# Z05_C8V_A_01.net
KiCad netlist of a schematic drawn in EAGLE
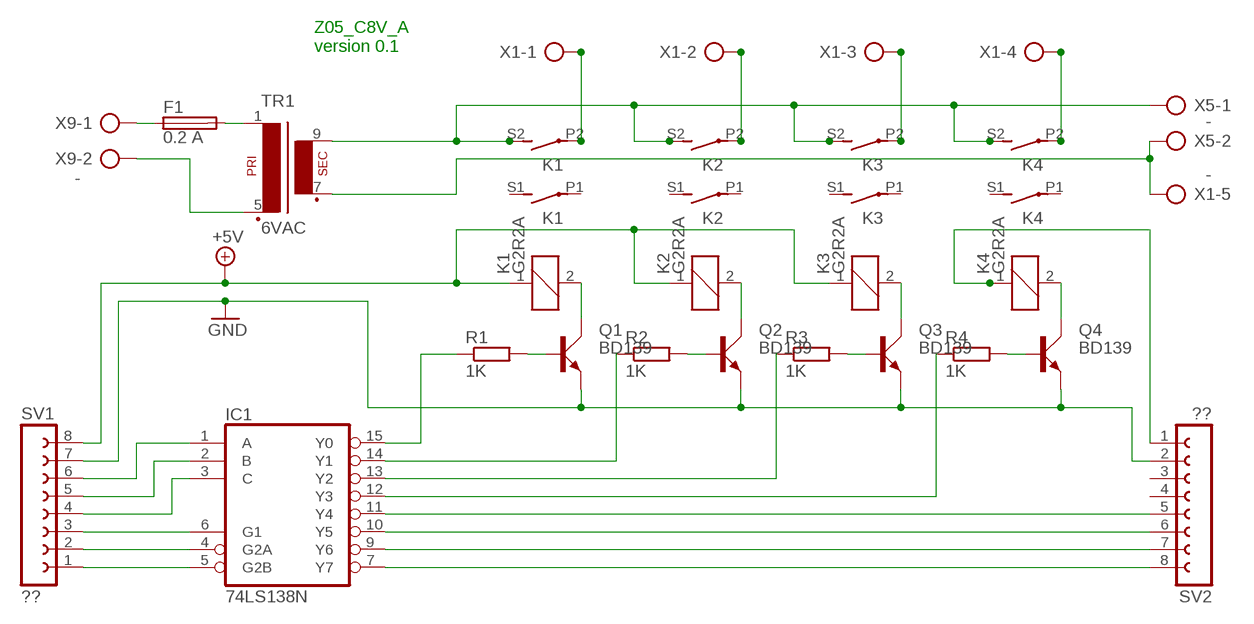
[diagram p0: schematic, sheet 1]

(export (version "E")
  (design (tool "Eeschema 10.0.6"))
  (components
    (comp (ref "F1")
      (value "0.2 A")
      (footprint "eagle-import:GSH15")
      (fields (field (name "MPN") "64900001039"))
      (libsource (lib "eagle-import") (part "GSH15"))
    )
    (comp (ref "IC1")
      (value "74LS138N")
      (footprint "eagle-import:DIL16")
      (libsource (lib "eagle-import") (part "74138NLS"))
    )
    (comp (ref "K1")
      (value "G2R2A")
      (footprint "eagle-import:G2R2A")
      (fields (field (name "MPN") "G2R-2A-DC24"))
      (libsource (lib "eagle-import") (part "G2R2A"))
    )
    (comp (ref "K2")
      (value "G2R2A")
      (footprint "eagle-import:G2R2A")
      (fields (field (name "MPN") "G2R-2A-DC24"))
      (libsource (lib "eagle-import") (part "G2R2A"))
    )
    (comp (ref "K3")
      (value "G2R2A")
      (footprint "eagle-import:G2R2A")
      (fields (field (name "MPN") "G2R-2A-DC24"))
      (libsource (lib "eagle-import") (part "G2R2A"))
    )
    (comp (ref "K4")
      (value "G2R2A")
      (footprint "eagle-import:G2R2A")
      (fields (field (name "MPN") "G2R-2A-DC24"))
      (libsource (lib "eagle-import") (part "G2R2A"))
    )
    (comp (ref "Q1")
      (value "BD139")
      (footprint "eagle-import:TO126AV")
      (libsource (lib "eagle-import") (part "BD139"))
    )
    (comp (ref "Q2")
      (value "BD139")
      (footprint "eagle-import:TO126AV")
      (libsource (lib "eagle-import") (part "BD139"))
    )
    (comp (ref "Q3")
      (value "BD139")
      (footprint "eagle-import:TO126AV")
      (libsource (lib "eagle-import") (part "BD139"))
    )
    (comp (ref "Q4")
      (value "BD139")
      (footprint "eagle-import:TO126AV")
      (libsource (lib "eagle-import") (part "BD139"))
    )
    (comp (ref "R1")
      (value "1K")
      (footprint "eagle-import:0204_7")
      (libsource (lib "eagle-import") (part "R-EU_0204/7"))
    )
    (comp (ref "R2")
      (value "1K")
      (footprint "eagle-import:0204_7")
      (libsource (lib "eagle-import") (part "R-EU_0204/7"))
    )
    (comp (ref "R3")
      (value "1K")
      (footprint "eagle-import:0204_7")
      (libsource (lib "eagle-import") (part "R-EU_0204/7"))
    )
    (comp (ref "R4")
      (value "1K")
      (footprint "eagle-import:0204_7")
      (libsource (lib "eagle-import") (part "R-EU_0204/7"))
    )
    (comp (ref "SV1")
      (value "??")
      (footprint "eagle-import:FE08W")
      (libsource (lib "eagle-import") (part "FE08W"))
    )
    (comp (ref "SV2")
      (value "??")
      (footprint "eagle-import:FE08W")
      (fields (field (name "OC_FARNELL") "unknown") (field (name "OC_NEWARK") "unknown"))
      (libsource (lib "eagle-import") (part "FE08W"))
    )
    (comp (ref "TR1")
      (value "6VAC")
      (footprint "eagle-import:EI42-1")
      (libsource (lib "eagle-import") (part "EI42-1"))
    )
    (comp (ref "X1")
      (value "-")
      (footprint "eagle-import:AK300_5")
      (libsource (lib "eagle-import") (part "AK300/5"))
    )
    (comp (ref "X5")
      (value "-")
      (footprint "eagle-import:AK300_2")
      (libsource (lib "eagle-import") (part "AK300/2"))
    )
    (comp (ref "X9")
      (value "-")
      (footprint "eagle-import:AK300_2")
      (libsource (lib "eagle-import") (part "AK300/2"))
    )
  )
  (nets
    (net (code "1") (name "+5V") (class "Default")
      (node (ref "K1") (pin "1") (pinfunction "1_1") (pintype "passive"))
      (node (ref "K2") (pin "1") (pinfunction "1_1") (pintype "passive"))
      (node (ref "K3") (pin "1") (pinfunction "1_1") (pintype "passive"))
      (node (ref "SV1") (pin "8") (pinfunction "8_8") (pintype "passive"))
    )
    (net (code "2") (name "/N$38") (class "Default")
      (node (ref "K1") (pin "P2") (pinfunction "P_P2") (pintype "passive"))
      (node (ref "K2") (pin "P2") (pinfunction "P_P2") (pintype "passive"))
      (node (ref "K3") (pin "P2") (pinfunction "P_P2") (pintype "passive"))
      (node (ref "K4") (pin "P2") (pinfunction "P_P2") (pintype "passive"))
      (node (ref "X1") (pin "1") (pinfunction "KL_1") (pintype "passive"))
      (node (ref "X1") (pin "2") (pinfunction "KL_2") (pintype "passive"))
      (node (ref "X1") (pin "3") (pinfunction "KL_3") (pintype "passive"))
      (node (ref "X1") (pin "4") (pinfunction "KL_4") (pintype "passive"))
    )
    (net (code "3") (name "GND") (class "Default")
      (node (ref "Q1") (pin "E") (pinfunction "E_E") (pintype "passive"))
      (node (ref "Q2") (pin "E") (pinfunction "E_E") (pintype "passive"))
      (node (ref "Q3") (pin "E") (pinfunction "E_E") (pintype "passive"))
      (node (ref "Q4") (pin "E") (pinfunction "E_E") (pintype "passive"))
      (node (ref "SV1") (pin "7") (pinfunction "7_7") (pintype "passive"))
      (node (ref "SV2") (pin "2") (pinfunction "2_2") (pintype "passive"))
    )
    (net (code "4") (name "Net-(IC1A-A)") (class "Default")
      (node (ref "IC1") (pin "1") (pinfunction "A_1") (pintype "input"))
      (node (ref "SV1") (pin "6") (pinfunction "6_6") (pintype "passive"))
    )
    (net (code "5") (name "Net-(IC1A-B)") (class "Default")
      (node (ref "IC1") (pin "2") (pinfunction "B_2") (pintype "input"))
      (node (ref "SV1") (pin "5") (pinfunction "5_5") (pintype "passive"))
    )
    (net (code "6") (name "Net-(IC1A-C)") (class "Default")
      (node (ref "IC1") (pin "3") (pinfunction "C_3") (pintype "input"))
      (node (ref "SV1") (pin "4") (pinfunction "4_4") (pintype "passive"))
    )
    (net (code "7") (name "Net-(IC1A-G1)") (class "Default")
      (node (ref "IC1") (pin "6") (pinfunction "G1_6") (pintype "input"))
      (node (ref "SV1") (pin "3") (pinfunction "3_3") (pintype "passive"))
    )
    (net (code "8") (name "Net-(IC1A-G2A)") (class "Default")
      (node (ref "IC1") (pin "4") (pinfunction "G2A_4") (pintype "input"))
      (node (ref "SV1") (pin "2") (pinfunction "2_2") (pintype "passive"))
    )
    (net (code "9") (name "Net-(IC1A-G2B)") (class "Default")
      (node (ref "IC1") (pin "5") (pinfunction "G2B_5") (pintype "input"))
      (node (ref "SV1") (pin "1") (pinfunction "1_1") (pintype "passive"))
    )
    (net (code "10") (name "Net-(IC1A-Y0)") (class "Default")
      (node (ref "IC1") (pin "15") (pinfunction "Y0_15") (pintype "output"))
      (node (ref "R1") (pin "1") (pinfunction "1_1") (pintype "passive"))
    )
    (net (code "11") (name "Net-(IC1A-Y1)") (class "Default")
      (node (ref "IC1") (pin "14") (pinfunction "Y1_14") (pintype "output"))
      (node (ref "R2") (pin "1") (pinfunction "1_1") (pintype "passive"))
    )
    (net (code "12") (name "Net-(IC1A-Y2)") (class "Default")
      (node (ref "IC1") (pin "13") (pinfunction "Y2_13") (pintype "output"))
      (node (ref "R3") (pin "1") (pinfunction "1_1") (pintype "passive"))
    )
    (net (code "13") (name "Net-(IC1A-Y3)") (class "Default")
      (node (ref "IC1") (pin "12") (pinfunction "Y3_12") (pintype "output"))
      (node (ref "R4") (pin "1") (pinfunction "1_1") (pintype "passive"))
    )
    (net (code "14") (name "Net-(IC1A-Y4)") (class "Default")
      (node (ref "IC1") (pin "11") (pinfunction "Y4_11") (pintype "output"))
      (node (ref "SV2") (pin "5") (pinfunction "5_5") (pintype "passive"))
    )
    (net (code "15") (name "Net-(IC1A-Y5)") (class "Default")
      (node (ref "IC1") (pin "10") (pinfunction "Y5_10") (pintype "output"))
      (node (ref "SV2") (pin "6") (pinfunction "6_6") (pintype "passive"))
    )
    (net (code "16") (name "Net-(IC1A-Y6)") (class "Default")
      (node (ref "IC1") (pin "9") (pinfunction "Y6_9") (pintype "output"))
      (node (ref "SV2") (pin "7") (pinfunction "7_7") (pintype "passive"))
    )
    (net (code "17") (name "Net-(IC1A-Y7)") (class "Default")
      (node (ref "IC1") (pin "7") (pinfunction "Y7_7") (pintype "output"))
      (node (ref "SV2") (pin "8") (pinfunction "8_8") (pintype "passive"))
    )
    (net (code "18") (name "Net-(K1-Pad2)") (class "Default")
      (node (ref "K1") (pin "2") (pinfunction "2_2") (pintype "passive"))
      (node (ref "Q1") (pin "C") (pinfunction "C_C") (pintype "passive"))
    )
    (net (code "19") (name "Net-(K1C-S)") (class "Default")
      (node (ref "K1") (pin "S2") (pinfunction "S_S2") (pintype "passive"))
      (node (ref "K2") (pin "S2") (pinfunction "S_S2") (pintype "passive"))
      (node (ref "K3") (pin "S2") (pinfunction "S_S2") (pintype "passive"))
      (node (ref "K4") (pin "S2") (pinfunction "S_S2") (pintype "passive"))
      (node (ref "TR1") (pin "9") (pinfunction "S4_9") (pintype "passive"))
      (node (ref "X5") (pin "1") (pinfunction "KL_1") (pintype "passive"))
    )
    (net (code "20") (name "Net-(K2-Pad2)") (class "Default")
      (node (ref "K2") (pin "2") (pinfunction "2_2") (pintype "passive"))
      (node (ref "Q2") (pin "C") (pinfunction "C_C") (pintype "passive"))
    )
    (net (code "21") (name "Net-(K3-Pad2)") (class "Default")
      (node (ref "K3") (pin "2") (pinfunction "2_2") (pintype "passive"))
      (node (ref "Q3") (pin "C") (pinfunction "C_C") (pintype "passive"))
    )
    (net (code "22") (name "Net-(K4-Pad1)") (class "Default")
      (node (ref "K4") (pin "1") (pinfunction "1_1") (pintype "passive"))
      (node (ref "SV2") (pin "1") (pinfunction "1_1") (pintype "passive"))
    )
    (net (code "23") (name "Net-(K4-Pad2)") (class "Default")
      (node (ref "K4") (pin "2") (pinfunction "2_2") (pintype "passive"))
      (node (ref "Q4") (pin "C") (pinfunction "C_C") (pintype "passive"))
    )
    (net (code "24") (name "Net-(Q1-PadB)") (class "Default")
      (node (ref "Q1") (pin "B") (pinfunction "B_B") (pintype "passive"))
      (node (ref "R1") (pin "2") (pinfunction "2_2") (pintype "passive"))
    )
    (net (code "25") (name "Net-(Q2-PadB)") (class "Default")
      (node (ref "Q2") (pin "B") (pinfunction "B_B") (pintype "passive"))
      (node (ref "R2") (pin "2") (pinfunction "2_2") (pintype "passive"))
    )
    (net (code "26") (name "Net-(Q3-PadB)") (class "Default")
      (node (ref "Q3") (pin "B") (pinfunction "B_B") (pintype "passive"))
      (node (ref "R3") (pin "2") (pinfunction "2_2") (pintype "passive"))
    )
    (net (code "27") (name "Net-(Q4-PadB)") (class "Default")
      (node (ref "Q4") (pin "B") (pinfunction "B_B") (pintype "passive"))
      (node (ref "R4") (pin "2") (pinfunction "2_2") (pintype "passive"))
    )
    (net (code "28") (name "Net-(TR1-P1)") (class "Default")
      (node (ref "F1") (pin "2") (pinfunction "2_2") (pintype "passive"))
      (node (ref "TR1") (pin "1") (pinfunction "P1_1") (pintype "passive"))
    )
    (net (code "29") (name "Net-(TR1-P2)") (class "Default")
      (node (ref "TR1") (pin "5") (pinfunction "P2_5") (pintype "passive"))
      (node (ref "X9") (pin "2") (pinfunction "KL_2") (pintype "passive"))
    )
    (net (code "30") (name "Net-(TR1-S3)") (class "Default")
      (node (ref "TR1") (pin "7") (pinfunction "S3_7") (pintype "passive"))
      (node (ref "X1") (pin "5") (pinfunction "KL_5") (pintype "passive"))
      (node (ref "X5") (pin "2") (pinfunction "KL_2") (pintype "passive"))
    )
    (net (code "31") (name "Net-(X9A-KL)") (class "Default")
      (node (ref "F1") (pin "1") (pinfunction "1_1") (pintype "passive"))
      (node (ref "X9") (pin "1") (pinfunction "KL_1") (pintype "passive"))
    )
    (net (code "32") (name "unconnected-(K1B-P-PadP1)") (class "Default")
      (node (ref "K1") (pin "P1") (pinfunction "P_P1") (pintype "passive"))
    )
    (net (code "33") (name "unconnected-(K1B-S-PadS1)") (class "Default")
      (node (ref "K1") (pin "S1") (pinfunction "S_S1") (pintype "passive"))
    )
    (net (code "34") (name "unconnected-(K2B-P-PadP1)") (class "Default")
      (node (ref "K2") (pin "P1") (pinfunction "P_P1") (pintype "passive"))
    )
    (net (code "35") (name "unconnected-(K2B-S-PadS1)") (class "Default")
      (node (ref "K2") (pin "S1") (pinfunction "S_S1") (pintype "passive"))
    )
    (net (code "36") (name "unconnected-(K3B-P-PadP1)") (class "Default")
      (node (ref "K3") (pin "P1") (pinfunction "P_P1") (pintype "passive"))
    )
    (net (code "37") (name "unconnected-(K3B-S-PadS1)") (class "Default")
      (node (ref "K3") (pin "S1") (pinfunction "S_S1") (pintype "passive"))
    )
    (net (code "38") (name "unconnected-(K4B-P-PadP1)") (class "Default")
      (node (ref "K4") (pin "P1") (pinfunction "P_P1") (pintype "passive"))
    )
    (net (code "39") (name "unconnected-(K4B-S-PadS1)") (class "Default")
      (node (ref "K4") (pin "S1") (pinfunction "S_S1") (pintype "passive"))
    )
    (net (code "40") (name "unconnected-(SV2-Pad3)") (class "Default")
      (node (ref "SV2") (pin "3") (pinfunction "3_3") (pintype "passive"))
    )
    (net (code "41") (name "unconnected-(SV2-Pad4)") (class "Default")
      (node (ref "SV2") (pin "4") (pinfunction "4_4") (pintype "passive"))
    )
  )
)
